# cdf-modular-bridge.net
KiCad netlist of a schematic drawn in EAGLE
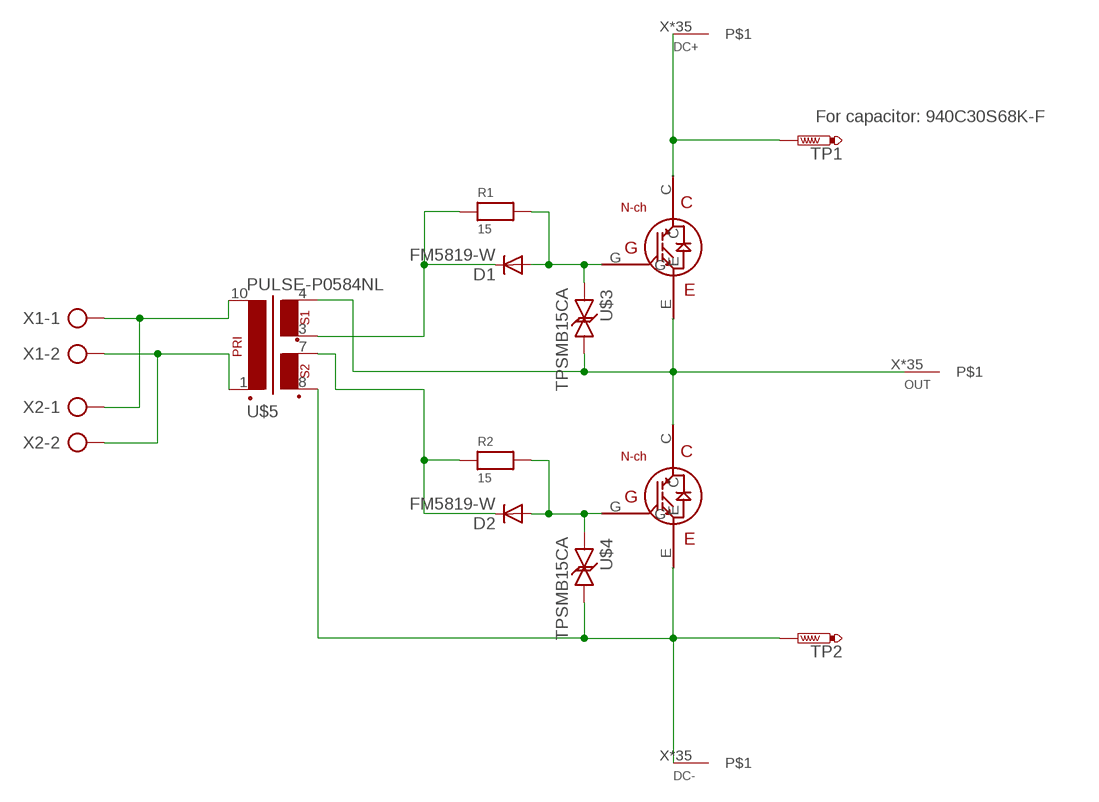
[diagram p0: schematic, sheet 1]

(export (version "E")
  (design (tool "Eeschema 10.0.6"))
  (components
    (comp (ref "D1")
      (value "FM5819-W")
      (footprint "eagle-import:DO214AC")
      (fields (field (name "MF") "Fairchild") (field (name "MPN") "S1A"))
      (libsource (lib "eagle-import") (part "S1A"))
    )
    (comp (ref "D2")
      (value "FM5819-W")
      (footprint "eagle-import:DO214AC")
      (fields (field (name "MF") "Fairchild") (field (name "MPN") "S1A"))
      (libsource (lib "eagle-import") (part "S1A"))
    )
    (comp (ref "DC+")
      (value "BIG-ASS-HOLE")
      (footprint "eagle-import:BIG-ASS-HOLE")
      (libsource (lib "eagle-import") (part "BIG-ASS-HOLE"))
    )
    (comp (ref "DC-")
      (value "BIG-ASS-HOLE")
      (footprint "eagle-import:BIG-ASS-HOLE")
      (libsource (lib "eagle-import") (part "BIG-ASS-HOLE"))
    )
    (comp (ref "OUT")
      (value "BIG-ASS-HOLE")
      (footprint "eagle-import:BIG-ASS-HOLE")
      (libsource (lib "eagle-import") (part "BIG-ASS-HOLE"))
    )
    (comp (ref "R1")
      (value "15")
      (footprint "eagle-import:1206")
      (libsource (lib "eagle-import") (part "RESISTOR1206"))
    )
    (comp (ref "R2")
      (value "15")
      (footprint "eagle-import:1206")
      (libsource (lib "eagle-import") (part "RESISTOR1206"))
    )
    (comp (ref "TP1")
      (value "PTR1PAD1-17")
      (footprint "eagle-import:P1-17")
      (libsource (lib "eagle-import") (part "PTR1PAD1-17"))
    )
    (comp (ref "TP2")
      (value "PTR1PAD1-17")
      (footprint "eagle-import:P1-17")
      (libsource (lib "eagle-import") (part "PTR1PAD1-17"))
    )
    (comp (ref "U$1")
      (value "Ixgh48n60a3")
      (footprint "eagle-import:IXGH40N60A")
      (libsource (lib "eagle-import") (part "IXGH40N60A"))
    )
    (comp (ref "U$2")
      (value "Ixgh48n60a3")
      (footprint "eagle-import:IXGH40N60A")
      (libsource (lib "eagle-import") (part "IXGH40N60A"))
    )
    (comp (ref "U$3")
      (value "TPSMB15CA")
      (footprint "eagle-import:TPSMB15CA")
      (libsource (lib "eagle-import") (part "TPSMB15CA"))
    )
    (comp (ref "U$4")
      (value "TPSMB15CA")
      (footprint "eagle-import:TPSMB15CA")
      (libsource (lib "eagle-import") (part "TPSMB15CA"))
    )
    (comp (ref "U$5")
      (value "PULSE-P0584NL")
      (footprint "eagle-import:PULSE-P0584NL")
      (libsource (lib "eagle-import") (part "PULSE-P0584NL"))
    )
    (comp (ref "X1")
      (value "AK500/2")
      (footprint "eagle-import:AK500_2")
      (libsource (lib "eagle-import") (part "AK500/2"))
    )
    (comp (ref "X2")
      (value "AK500/2")
      (footprint "eagle-import:AK500_2")
      (libsource (lib "eagle-import") (part "AK500/2"))
    )
  )
  (nets
    (net (code "1") (name "Net-(D1-PadA)") (class "Default")
      (node (ref "D1") (pin "A") (pinfunction "A_A") (pintype "passive"))
      (node (ref "R1") (pin "2") (pinfunction "2_2") (pintype "passive"))
      (node (ref "U$1") (pin "G") (pinfunction "G_G") (pintype "bidirectional"))
      (node (ref "U$3") (pin "P$1") (pinfunction "P$1_P$1") (pintype "passive"))
    )
    (net (code "2") (name "Net-(D2-PadA)") (class "Default")
      (node (ref "D2") (pin "A") (pinfunction "A_A") (pintype "passive"))
      (node (ref "R2") (pin "2") (pinfunction "2_2") (pintype "passive"))
      (node (ref "U$2") (pin "G") (pinfunction "G_G") (pintype "bidirectional"))
      (node (ref "U$4") (pin "P$1") (pinfunction "P$1_P$1") (pintype "passive"))
    )
    (net (code "3") (name "Net-(DC+-P$1-PadX)") (class "Default")
      (node (ref "DC+") (pin "X") (pinfunction "P$1_X") (pintype "bidirectional"))
      (node (ref "DC+") (pin "X@1") (pinfunction "P$1_X@1") (pintype "bidirectional"))
      (node (ref "DC+") (pin "X@10") (pinfunction "P$1_X@10") (pintype "bidirectional"))
      (node (ref "DC+") (pin "X@11") (pinfunction "P$1_X@11") (pintype "bidirectional"))
      (node (ref "DC+") (pin "X@12") (pinfunction "P$1_X@12") (pintype "bidirectional"))
      (node (ref "DC+") (pin "X@120") (pinfunction "P$1_X@120") (pintype "bidirectional"))
      (node (ref "DC+") (pin "X@13") (pinfunction "P$1_X@13") (pintype "bidirectional"))
      (node (ref "DC+") (pin "X@14") (pinfunction "P$1_X@14") (pintype "bidirectional"))
      (node (ref "DC+") (pin "X@15") (pinfunction "P$1_X@15") (pintype "bidirectional"))
      (node (ref "DC+") (pin "X@16") (pinfunction "P$1_X@16") (pintype "bidirectional"))
      (node (ref "DC+") (pin "X@17") (pinfunction "P$1_X@17") (pintype "bidirectional"))
      (node (ref "DC+") (pin "X@18") (pinfunction "P$1_X@18") (pintype "bidirectional"))
      (node (ref "DC+") (pin "X@19") (pinfunction "P$1_X@19") (pintype "bidirectional"))
      (node (ref "DC+") (pin "X@2") (pinfunction "P$1_X@2") (pintype "bidirectional"))
      (node (ref "DC+") (pin "X@20") (pinfunction "P$1_X@20") (pintype "bidirectional"))
      (node (ref "DC+") (pin "X@21") (pinfunction "P$1_X@21") (pintype "bidirectional"))
      (node (ref "DC+") (pin "X@22") (pinfunction "P$1_X@22") (pintype "bidirectional"))
      (node (ref "DC+") (pin "X@23") (pinfunction "P$1_X@23") (pintype "bidirectional"))
      (node (ref "DC+") (pin "X@24") (pinfunction "P$1_X@24") (pintype "bidirectional"))
      (node (ref "DC+") (pin "X@25") (pinfunction "P$1_X@25") (pintype "bidirectional"))
      (node (ref "DC+") (pin "X@26") (pinfunction "P$1_X@26") (pintype "bidirectional"))
      (node (ref "DC+") (pin "X@27") (pinfunction "P$1_X@27") (pintype "bidirectional"))
      (node (ref "DC+") (pin "X@28") (pinfunction "P$1_X@28") (pintype "bidirectional"))
      (node (ref "DC+") (pin "X@29") (pinfunction "P$1_X@29") (pintype "bidirectional"))
      (node (ref "DC+") (pin "X@3") (pinfunction "P$1_X@3") (pintype "bidirectional"))
      (node (ref "DC+") (pin "X@30") (pinfunction "P$1_X@30") (pintype "bidirectional"))
      (node (ref "DC+") (pin "X@31") (pinfunction "P$1_X@31") (pintype "bidirectional"))
      (node (ref "DC+") (pin "X@32") (pinfunction "P$1_X@32") (pintype "bidirectional"))
      (node (ref "DC+") (pin "X@34") (pinfunction "P$1_X@34") (pintype "bidirectional"))
      (node (ref "DC+") (pin "X@4") (pinfunction "P$1_X@4") (pintype "bidirectional"))
      (node (ref "DC+") (pin "X@5") (pinfunction "P$1_X@5") (pintype "bidirectional"))
      (node (ref "DC+") (pin "X@6") (pinfunction "P$1_X@6") (pintype "bidirectional"))
      (node (ref "DC+") (pin "X@7") (pinfunction "P$1_X@7") (pintype "bidirectional"))
      (node (ref "DC+") (pin "X@8") (pinfunction "P$1_X@8") (pintype "bidirectional"))
      (node (ref "DC+") (pin "X@9") (pinfunction "P$1_X@9") (pintype "bidirectional"))
      (node (ref "TP1") (pin "TP") (pinfunction "TP_TP") (pintype "input"))
      (node (ref "U$1") (pin "C") (pinfunction "C_C") (pintype "bidirectional"))
    )
    (net (code "4") (name "Net-(U$5-PRI_NEG)") (class "Default")
      (node (ref "U$5") (pin "10") (pinfunction "PRI_NEG_10") (pintype "passive"))
      (node (ref "X1") (pin "1") (pinfunction "KL_1") (pintype "passive"))
      (node (ref "X2") (pin "1") (pinfunction "KL_1") (pintype "passive"))
    )
    (net (code "5") (name "Net-(U$5-PRI_POS)") (class "Default")
      (node (ref "U$5") (pin "1") (pinfunction "PRI_POS_1") (pintype "passive"))
      (node (ref "X1") (pin "2") (pinfunction "KL_2") (pintype "passive"))
      (node (ref "X2") (pin "2") (pinfunction "KL_2") (pintype "passive"))
    )
    (net (code "6") (name "Net-(U$5-SEC1_NEG)") (class "Default")
      (node (ref "OUT") (pin "X") (pinfunction "P$1_X") (pintype "bidirectional"))
      (node (ref "OUT") (pin "X@1") (pinfunction "P$1_X@1") (pintype "bidirectional"))
      (node (ref "OUT") (pin "X@10") (pinfunction "P$1_X@10") (pintype "bidirectional"))
      (node (ref "OUT") (pin "X@11") (pinfunction "P$1_X@11") (pintype "bidirectional"))
      (node (ref "OUT") (pin "X@12") (pinfunction "P$1_X@12") (pintype "bidirectional"))
      (node (ref "OUT") (pin "X@120") (pinfunction "P$1_X@120") (pintype "bidirectional"))
      (node (ref "OUT") (pin "X@13") (pinfunction "P$1_X@13") (pintype "bidirectional"))
      (node (ref "OUT") (pin "X@14") (pinfunction "P$1_X@14") (pintype "bidirectional"))
      (node (ref "OUT") (pin "X@15") (pinfunction "P$1_X@15") (pintype "bidirectional"))
      (node (ref "OUT") (pin "X@16") (pinfunction "P$1_X@16") (pintype "bidirectional"))
      (node (ref "OUT") (pin "X@17") (pinfunction "P$1_X@17") (pintype "bidirectional"))
      (node (ref "OUT") (pin "X@18") (pinfunction "P$1_X@18") (pintype "bidirectional"))
      (node (ref "OUT") (pin "X@19") (pinfunction "P$1_X@19") (pintype "bidirectional"))
      (node (ref "OUT") (pin "X@2") (pinfunction "P$1_X@2") (pintype "bidirectional"))
      (node (ref "OUT") (pin "X@20") (pinfunction "P$1_X@20") (pintype "bidirectional"))
      (node (ref "OUT") (pin "X@21") (pinfunction "P$1_X@21") (pintype "bidirectional"))
      (node (ref "OUT") (pin "X@22") (pinfunction "P$1_X@22") (pintype "bidirectional"))
      (node (ref "OUT") (pin "X@23") (pinfunction "P$1_X@23") (pintype "bidirectional"))
      (node (ref "OUT") (pin "X@24") (pinfunction "P$1_X@24") (pintype "bidirectional"))
      (node (ref "OUT") (pin "X@25") (pinfunction "P$1_X@25") (pintype "bidirectional"))
      (node (ref "OUT") (pin "X@26") (pinfunction "P$1_X@26") (pintype "bidirectional"))
      (node (ref "OUT") (pin "X@27") (pinfunction "P$1_X@27") (pintype "bidirectional"))
      (node (ref "OUT") (pin "X@28") (pinfunction "P$1_X@28") (pintype "bidirectional"))
      (node (ref "OUT") (pin "X@29") (pinfunction "P$1_X@29") (pintype "bidirectional"))
      (node (ref "OUT") (pin "X@3") (pinfunction "P$1_X@3") (pintype "bidirectional"))
      (node (ref "OUT") (pin "X@30") (pinfunction "P$1_X@30") (pintype "bidirectional"))
      (node (ref "OUT") (pin "X@31") (pinfunction "P$1_X@31") (pintype "bidirectional"))
      (node (ref "OUT") (pin "X@32") (pinfunction "P$1_X@32") (pintype "bidirectional"))
      (node (ref "OUT") (pin "X@34") (pinfunction "P$1_X@34") (pintype "bidirectional"))
      (node (ref "OUT") (pin "X@4") (pinfunction "P$1_X@4") (pintype "bidirectional"))
      (node (ref "OUT") (pin "X@5") (pinfunction "P$1_X@5") (pintype "bidirectional"))
      (node (ref "OUT") (pin "X@6") (pinfunction "P$1_X@6") (pintype "bidirectional"))
      (node (ref "OUT") (pin "X@7") (pinfunction "P$1_X@7") (pintype "bidirectional"))
      (node (ref "OUT") (pin "X@8") (pinfunction "P$1_X@8") (pintype "bidirectional"))
      (node (ref "OUT") (pin "X@9") (pinfunction "P$1_X@9") (pintype "bidirectional"))
      (node (ref "U$1") (pin "E") (pinfunction "E_E") (pintype "bidirectional"))
      (node (ref "U$2") (pin "C") (pinfunction "C_C") (pintype "bidirectional"))
      (node (ref "U$3") (pin "P$2") (pinfunction "P$2_P$2") (pintype "passive"))
      (node (ref "U$5") (pin "4") (pinfunction "SEC1_NEG_4") (pintype "passive"))
    )
    (net (code "7") (name "Net-(U$5-SEC1_POS)") (class "Default")
      (node (ref "D1") (pin "C") (pinfunction "C_C") (pintype "passive"))
      (node (ref "R1") (pin "1") (pinfunction "1_1") (pintype "passive"))
      (node (ref "U$5") (pin "3") (pinfunction "SEC1_POS_3") (pintype "passive"))
    )
    (net (code "8") (name "Net-(U$5-SEC2_NEG)") (class "Default")
      (node (ref "D2") (pin "C") (pinfunction "C_C") (pintype "passive"))
      (node (ref "R2") (pin "1") (pinfunction "1_1") (pintype "passive"))
      (node (ref "U$5") (pin "7") (pinfunction "SEC2_NEG_7") (pintype "passive"))
    )
    (net (code "9") (name "Net-(U$5-SEC2_POS)") (class "Default")
      (node (ref "DC-") (pin "X") (pinfunction "P$1_X") (pintype "bidirectional"))
      (node (ref "DC-") (pin "X@1") (pinfunction "P$1_X@1") (pintype "bidirectional"))
      (node (ref "DC-") (pin "X@10") (pinfunction "P$1_X@10") (pintype "bidirectional"))
      (node (ref "DC-") (pin "X@11") (pinfunction "P$1_X@11") (pintype "bidirectional"))
      (node (ref "DC-") (pin "X@12") (pinfunction "P$1_X@12") (pintype "bidirectional"))
      (node (ref "DC-") (pin "X@120") (pinfunction "P$1_X@120") (pintype "bidirectional"))
      (node (ref "DC-") (pin "X@13") (pinfunction "P$1_X@13") (pintype "bidirectional"))
      (node (ref "DC-") (pin "X@14") (pinfunction "P$1_X@14") (pintype "bidirectional"))
      (node (ref "DC-") (pin "X@15") (pinfunction "P$1_X@15") (pintype "bidirectional"))
      (node (ref "DC-") (pin "X@16") (pinfunction "P$1_X@16") (pintype "bidirectional"))
      (node (ref "DC-") (pin "X@17") (pinfunction "P$1_X@17") (pintype "bidirectional"))
      (node (ref "DC-") (pin "X@18") (pinfunction "P$1_X@18") (pintype "bidirectional"))
      (node (ref "DC-") (pin "X@19") (pinfunction "P$1_X@19") (pintype "bidirectional"))
      (node (ref "DC-") (pin "X@2") (pinfunction "P$1_X@2") (pintype "bidirectional"))
      (node (ref "DC-") (pin "X@20") (pinfunction "P$1_X@20") (pintype "bidirectional"))
      (node (ref "DC-") (pin "X@21") (pinfunction "P$1_X@21") (pintype "bidirectional"))
      (node (ref "DC-") (pin "X@22") (pinfunction "P$1_X@22") (pintype "bidirectional"))
      (node (ref "DC-") (pin "X@23") (pinfunction "P$1_X@23") (pintype "bidirectional"))
      (node (ref "DC-") (pin "X@24") (pinfunction "P$1_X@24") (pintype "bidirectional"))
      (node (ref "DC-") (pin "X@25") (pinfunction "P$1_X@25") (pintype "bidirectional"))
      (node (ref "DC-") (pin "X@26") (pinfunction "P$1_X@26") (pintype "bidirectional"))
      (node (ref "DC-") (pin "X@27") (pinfunction "P$1_X@27") (pintype "bidirectional"))
      (node (ref "DC-") (pin "X@28") (pinfunction "P$1_X@28") (pintype "bidirectional"))
      (node (ref "DC-") (pin "X@29") (pinfunction "P$1_X@29") (pintype "bidirectional"))
      (node (ref "DC-") (pin "X@3") (pinfunction "P$1_X@3") (pintype "bidirectional"))
      (node (ref "DC-") (pin "X@30") (pinfunction "P$1_X@30") (pintype "bidirectional"))
      (node (ref "DC-") (pin "X@31") (pinfunction "P$1_X@31") (pintype "bidirectional"))
      (node (ref "DC-") (pin "X@32") (pinfunction "P$1_X@32") (pintype "bidirectional"))
      (node (ref "DC-") (pin "X@34") (pinfunction "P$1_X@34") (pintype "bidirectional"))
      (node (ref "DC-") (pin "X@4") (pinfunction "P$1_X@4") (pintype "bidirectional"))
      (node (ref "DC-") (pin "X@5") (pinfunction "P$1_X@5") (pintype "bidirectional"))
      (node (ref "DC-") (pin "X@6") (pinfunction "P$1_X@6") (pintype "bidirectional"))
      (node (ref "DC-") (pin "X@7") (pinfunction "P$1_X@7") (pintype "bidirectional"))
      (node (ref "DC-") (pin "X@8") (pinfunction "P$1_X@8") (pintype "bidirectional"))
      (node (ref "DC-") (pin "X@9") (pinfunction "P$1_X@9") (pintype "bidirectional"))
      (node (ref "TP2") (pin "TP") (pinfunction "TP_TP") (pintype "input"))
      (node (ref "U$2") (pin "E") (pinfunction "E_E") (pintype "bidirectional"))
      (node (ref "U$4") (pin "P$2") (pinfunction "P$2_P$2") (pintype "passive"))
      (node (ref "U$5") (pin "8") (pinfunction "SEC2_POS_8") (pintype "passive"))
    )
  )
)
